# DriveModule.net
KiCad netlist of a schematic drawn in Altium Designer
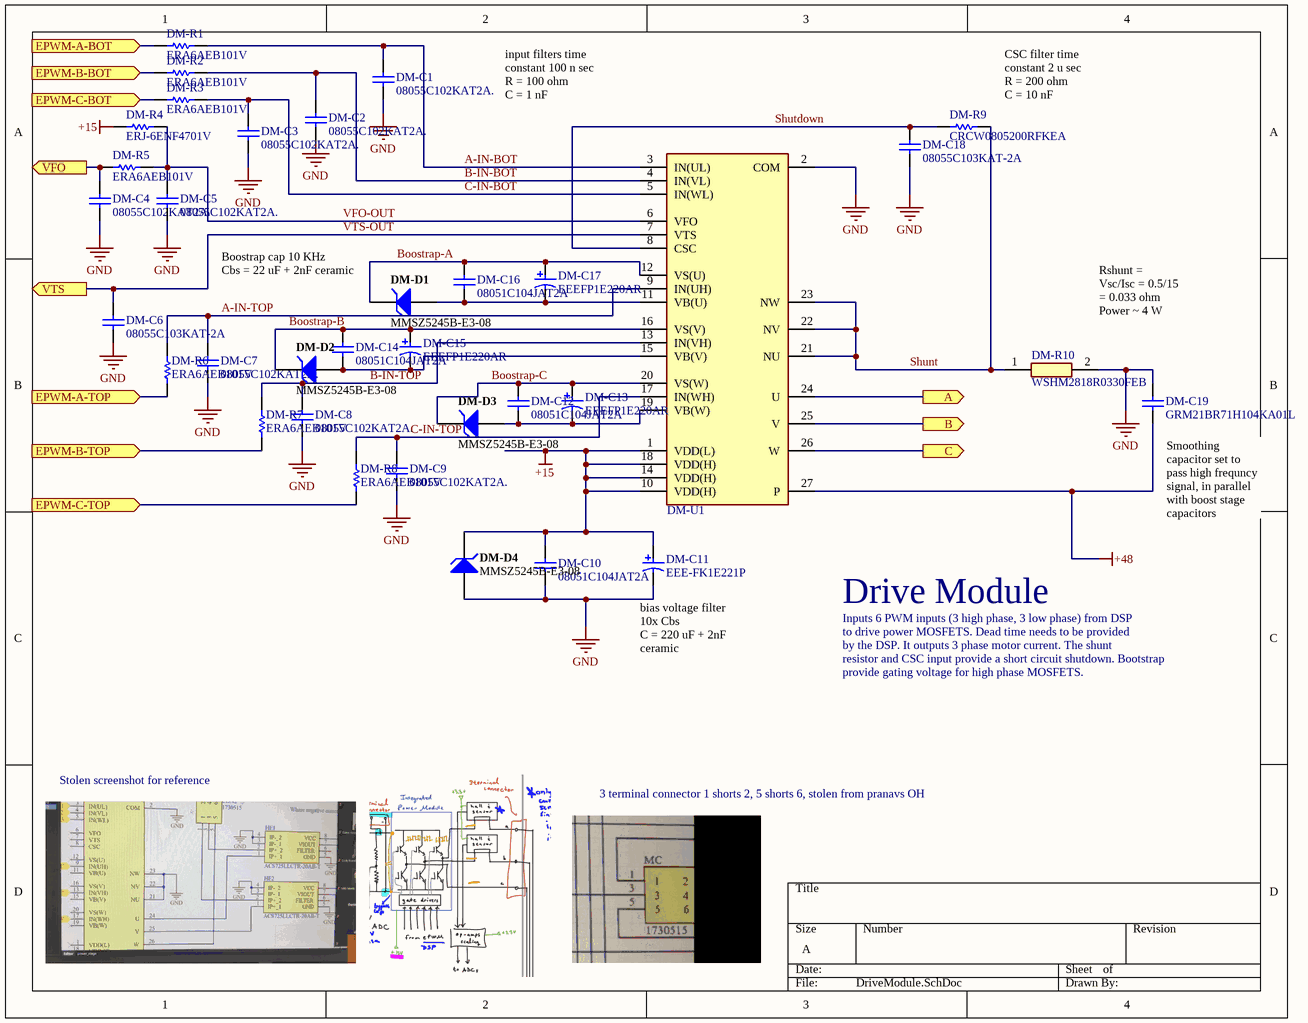
[diagram p0: DriveModule.SchDoc]

(export (version "E")
  (design (tool "Eeschema 10.0.6"))
  (components
    (comp (ref "DM-C1")
      (value "08055C102KAT2A.")
      (footprint "CAPC2013X94X50ML20T25")
      (description "1 nF cap")
      (fields (field (name "MANUFACTURER") "AVX Interconnect / Elco"))
      (libsource (lib "Altium Content Vault") (part "CAP"))
    )
    (comp (ref "DM-C2")
      (value "08055C102KAT2A.")
      (footprint "CAPC2013X94X50ML20T25")
      (description "1 nF cap")
      (fields (field (name "MANUFACTURER") "AVX Interconnect / Elco"))
      (libsource (lib "Altium Content Vault") (part "CAP"))
    )
    (comp (ref "DM-C3")
      (value "08055C102KAT2A.")
      (footprint "CAPC2013X94X50ML20T25")
      (description "1 nF cap")
      (fields (field (name "MANUFACTURER") "AVX Interconnect / Elco"))
      (libsource (lib "Altium Content Vault") (part "CAP"))
    )
    (comp (ref "DM-C4")
      (value "08055C102KAT2A.")
      (footprint "CAPC2013X94X50ML20T25")
      (description "1 nF cap")
      (fields (field (name "MANUFACTURER") "AVX Interconnect / Elco"))
      (libsource (lib "Altium Content Vault") (part "CAP"))
    )
    (comp (ref "DM-C5")
      (value "08055C102KAT2A.")
      (footprint "CAPC2013X94X50ML20T25")
      (description "1 nF cap")
      (fields (field (name "MANUFACTURER") "AVX Interconnect / Elco"))
      (libsource (lib "Altium Content Vault") (part "CAP"))
    )
    (comp (ref "DM-C6")
      (value "08055C103KAT-2A")
      (footprint "CAPC2013X94X50NL20T25")
      (description "10 nF cap")
      (fields (field (name "MANUFACTURER") "AVX Interconnect / Elco"))
      (libsource (lib "Altium Content Vault") (part "CAP"))
    )
    (comp (ref "DM-C7")
      (value "08055C102KAT2A.")
      (footprint "CAPC2013X94X50ML20T25")
      (description "1 nF cap")
      (fields (field (name "MANUFACTURER") "AVX Interconnect / Elco"))
      (libsource (lib "Altium Content Vault") (part "CAP"))
    )
    (comp (ref "DM-C8")
      (value "08055C102KAT2A.")
      (footprint "CAPC2013X94X50ML20T25")
      (description "1 nF cap")
      (fields (field (name "MANUFACTURER") "AVX Interconnect / Elco"))
      (libsource (lib "Altium Content Vault") (part "CAP"))
    )
    (comp (ref "DM-C9")
      (value "08055C102KAT2A.")
      (footprint "CAPC2013X94X50ML20T25")
      (description "1 nF cap")
      (fields (field (name "MANUFACTURER") "AVX Interconnect / Elco"))
      (libsource (lib "Altium Content Vault") (part "CAP"))
    )
    (comp (ref "DM-C10")
      (value "08051C104JAT2A")
      (footprint "CAPC2013X94X50ML20T25")
      (fields (field (name "MANUFACTURER") "AVX Interconnect / Elco"))
      (libsource (lib "Altium Content Vault") (part "CAP"))
    )
    (comp (ref "DM-C11")
      (value "EEE-FK1E221P")
      (footprint "PNSC-EEE-FK1E221P_N")
      (fields (field (name "MANUFACTURER") "Panasonic"))
      (libsource (lib "Altium Content Vault") (part "CAP-P-2"))
    )
    (comp (ref "DM-C12")
      (value "08051C104JAT2A")
      (footprint "CAPC2013X94X50ML20T25")
      (fields (field (name "MANUFACTURER") "AVX Interconnect / Elco"))
      (libsource (lib "Altium Content Vault") (part "CAP"))
    )
    (comp (ref "DM-C13")
      (value "EEEFP1E220AR")
      (footprint "PNSC-FP-V-C_V")
      (fields (field (name "MANUFACTURER") "Panasonic"))
      (libsource (lib "Altium Content Vault") (part "CAP-P-2"))
    )
    (comp (ref "DM-C14")
      (value "08051C104JAT2A")
      (footprint "CAPC2013X94X50ML20T25")
      (fields (field (name "MANUFACTURER") "AVX Interconnect / Elco"))
      (libsource (lib "Altium Content Vault") (part "CAP"))
    )
    (comp (ref "DM-C15")
      (value "EEEFP1E220AR")
      (footprint "PNSC-FP-V-C_V")
      (fields (field (name "MANUFACTURER") "Panasonic"))
      (libsource (lib "Altium Content Vault") (part "CAP-P-2"))
    )
    (comp (ref "DM-C16")
      (value "08051C104JAT2A")
      (footprint "CAPC2013X94X50ML20T25")
      (fields (field (name "MANUFACTURER") "AVX Interconnect / Elco"))
      (libsource (lib "Altium Content Vault") (part "CAP"))
    )
    (comp (ref "DM-C17")
      (value "EEEFP1E220AR")
      (footprint "PNSC-FP-V-C_V")
      (fields (field (name "MANUFACTURER") "Panasonic"))
      (libsource (lib "Altium Content Vault") (part "CAP-P-2"))
    )
    (comp (ref "DM-C18")
      (value "08055C103KAT-2A")
      (footprint "CAPC2013X94X50NL20T25")
      (description "10 nF cap")
      (fields (field (name "MANUFACTURER") "AVX Interconnect / Elco"))
      (libsource (lib "Altium Content Vault") (part "CAP"))
    )
    (comp (ref "DM-C19")
      (value "GRM21BR71H104KA01L")
      (footprint "CAPC2013X135X45ML10T25")
      (description "Chip Capacitor, 0.1 uF, +/- 10%, 50 V, -55 to 125 degC, 0805 (2012 Metric), RoHS, Tape and Reel")
      (fields (field (name "VOLTAGE") "50V") (field (name "TOLERANCE") "10%"))
      (libsource (lib "Altium Content Vault") (part "CAP-NP-2"))
    )
    (comp (ref "DM-D1")
      (value "MMSZ5245B-E3-08")
      (footprint "VISH-SOD-123-2_V")
      (description "Small Signal Zener Diode, 15 V +/- 5%, -55 to 155 degC, 2-Pin SOD-123, RoHS, Tape and Reel")
      (fields (field (name "MANUFACTURER") "Vishay Semiconductor") (field (name "TOLERANCE") "+/- 5%"))
      (libsource (lib "Altium Content Vault") (part "VISH-DZEN_A1K2-2"))
    )
    (comp (ref "DM-D2")
      (value "MMSZ5245B-E3-08")
      (footprint "VISH-SOD-123-2_V")
      (description "Small Signal Zener Diode, 15 V +/- 5%, -55 to 155 degC, 2-Pin SOD-123, RoHS, Tape and Reel")
      (fields (field (name "MANUFACTURER") "Vishay Semiconductor") (field (name "TOLERANCE") "+/- 5%"))
      (libsource (lib "Altium Content Vault") (part "VISH-DZEN_A1K2-2"))
    )
    (comp (ref "DM-D3")
      (value "MMSZ5245B-E3-08")
      (footprint "VISH-SOD-123-2_V")
      (description "Small Signal Zener Diode, 15 V +/- 5%, -55 to 155 degC, 2-Pin SOD-123, RoHS, Tape and Reel")
      (fields (field (name "MANUFACTURER") "Vishay Semiconductor") (field (name "TOLERANCE") "+/- 5%"))
      (libsource (lib "Altium Content Vault") (part "VISH-DZEN_A1K2-2"))
    )
    (comp (ref "DM-D4")
      (value "MMSZ5245B-E3-08")
      (footprint "VISH-SOD-123-2_V")
      (description "Small Signal Zener Diode, 15 V +/- 5%, -55 to 155 degC, 2-Pin SOD-123, RoHS, Tape and Reel")
      (fields (field (name "MANUFACTURER") "Vishay Semiconductor") (field (name "TOLERANCE") "+/- 5%"))
      (libsource (lib "Altium Content Vault") (part "VISH-DZEN_A1K2-2"))
    )
    (comp (ref "DM-R1")
      (value "ERA6AEB101V")
      (footprint "RESC2013X60X40ML20T25")
      (description "100 ohm resistor")
      (fields (field (name "MANUFACTURER") "Panasonic"))
      (libsource (lib "Altium Content Vault") (part "RES"))
    )
    (comp (ref "DM-R2")
      (value "ERA6AEB101V")
      (footprint "RESC2013X60X40ML20T25")
      (description "100 ohm resistor")
      (fields (field (name "MANUFACTURER") "Panasonic"))
      (libsource (lib "Altium Content Vault") (part "RES"))
    )
    (comp (ref "DM-R3")
      (value "ERA6AEB101V")
      (footprint "RESC2013X60X40ML20T25")
      (description "100 ohm resistor")
      (fields (field (name "MANUFACTURER") "Panasonic"))
      (libsource (lib "Altium Content Vault") (part "RES"))
    )
    (comp (ref "DM-R4")
      (value "ERJ-6ENF4701V")
      (footprint "RESC2013X70X40NL20T20")
      (description "Chip Resistor, 4.7 KOhm, +/- 1%, 0.125 W, -55 to 155 degC, 0805 (2012 Metric), RoHS, Tape and Reel")
      (fields (field (name "MANUFACTURER") "Panasonic"))
      (libsource (lib "Altium Content Vault") (part "RES-2"))
    )
    (comp (ref "DM-R5")
      (value "ERA6AEB101V")
      (footprint "RESC2013X60X40ML20T25")
      (fields (field (name "MANUFACTURER") "Panasonic"))
      (libsource (lib "Altium Content Vault") (part "RES"))
    )
    (comp (ref "DM-R6")
      (value "ERA6AEB101V")
      (footprint "RESC2013X60X40ML20T25")
      (description "100 ohm resistor")
      (fields (field (name "MANUFACTURER") "Panasonic"))
      (libsource (lib "Altium Content Vault") (part "RES"))
    )
    (comp (ref "DM-R7")
      (value "ERA6AEB101V")
      (footprint "RESC2013X60X40ML20T25")
      (description "100 ohm resistor")
      (fields (field (name "MANUFACTURER") "Panasonic"))
      (libsource (lib "Altium Content Vault") (part "RES"))
    )
    (comp (ref "DM-R8")
      (value "ERA6AEB101V")
      (footprint "RESC2013X60X40ML20T25")
      (description "100 ohm resistor")
      (fields (field (name "MANUFACTURER") "Panasonic"))
      (libsource (lib "Altium Content Vault") (part "RES"))
    )
    (comp (ref "DM-R9")
      (value "CRCW0805200RFKEA")
      (footprint "RESC2013X50X30NL20T20")
      (description "200 ohm resistor")
      (fields (field (name "MANUFACTURER") "Vishay Dale"))
      (libsource (lib "Altium Content Vault") (part "RES"))
    )
    (comp (ref "DM-R10")
      (value "WSHM2818R0330FEB")
      (footprint "SamacSys:WSHM2818R0330FEB")
      (description "Resistor")
      (fields (field (name "MOUSER PART NUMBER") "71-WSHM2818R0330FEB"))
      (libsource (lib "*") (part "WSHM2818R0330FEB"))
    )
    (comp (ref "DM-U1")
      (value "FNB34060T")
      (footprint "FNB34060T")
      (description "3 phase power module")
      (libsource (lib "ee_453_yourname") (part "FNB34060T"))
    )
  )
  (nets
    (net (code "1") (name "+15") (class "Default")
      (node (ref "DM-C10") (pin "2") (pinfunction "2_2") (pintype "passive"))
      (node (ref "DM-C11") (pin "1") (pinfunction "1_1") (pintype "passive"))
      (node (ref "DM-D4") (pin "2") (pinfunction "K_2") (pintype "passive"))
      (node (ref "DM-R4") (pin "1") (pinfunction "1_1") (pintype "passive"))
      (node (ref "DM-U1") (pin "1") (pinfunction "VDD(L)_1") (pintype "power_in"))
      (node (ref "DM-U1") (pin "10") (pinfunction "VDD(H)_10") (pintype "power_in"))
      (node (ref "DM-U1") (pin "14") (pinfunction "VDD(H)_14") (pintype "power_in"))
      (node (ref "DM-U1") (pin "18") (pinfunction "VDD(H)_18") (pintype "power_in"))
    )
    (net (code "2") (name "+48") (class "Default")
      (node (ref "DM-C19") (pin "1") (pinfunction "1_1") (pintype "passive"))
      (node (ref "DM-U1") (pin "27") (pinfunction "P_27") (pintype "passive"))
    )
    (net (code "3") (name "/A") (class "Default")
      (node (ref "DM-U1") (pin "24") (pinfunction "U_24") (pintype "passive"))
    )
    (net (code "4") (name "/A-IN-BOT") (class "Default")
      (node (ref "DM-C1") (pin "2") (pinfunction "2_2") (pintype "passive"))
      (node (ref "DM-R1") (pin "2") (pinfunction "2_2") (pintype "passive"))
      (node (ref "DM-U1") (pin "3") (pinfunction "IN(UL)_3") (pintype "passive"))
    )
    (net (code "5") (name "/A-IN-TOP") (class "Default")
      (node (ref "DM-C7") (pin "2") (pinfunction "2_2") (pintype "passive"))
      (node (ref "DM-R6") (pin "2") (pinfunction "2_2") (pintype "passive"))
      (node (ref "DM-U1") (pin "9") (pinfunction "IN(UH)_9") (pintype "passive"))
    )
    (net (code "6") (name "/B") (class "Default")
      (node (ref "DM-U1") (pin "25") (pinfunction "V_25") (pintype "passive"))
    )
    (net (code "7") (name "/B-IN-BOT") (class "Default")
      (node (ref "DM-C2") (pin "2") (pinfunction "2_2") (pintype "passive"))
      (node (ref "DM-R2") (pin "2") (pinfunction "2_2") (pintype "passive"))
      (node (ref "DM-U1") (pin "4") (pinfunction "IN(VL)_4") (pintype "passive"))
    )
    (net (code "8") (name "/B-IN-TOP") (class "Default")
      (node (ref "DM-C8") (pin "2") (pinfunction "2_2") (pintype "passive"))
      (node (ref "DM-R7") (pin "2") (pinfunction "2_2") (pintype "passive"))
      (node (ref "DM-U1") (pin "13") (pinfunction "IN(VH)_13") (pintype "passive"))
    )
    (net (code "9") (name "/Boostrap-A") (class "Default")
      (node (ref "DM-C16") (pin "2") (pinfunction "2_2") (pintype "passive"))
      (node (ref "DM-C17") (pin "1") (pinfunction "1_1") (pintype "passive"))
      (node (ref "DM-D1") (pin "2") (pinfunction "K_2") (pintype "passive"))
      (node (ref "DM-U1") (pin "12") (pinfunction "VS(U)_12") (pintype "power_in"))
    )
    (net (code "10") (name "/Boostrap-B") (class "Default")
      (node (ref "DM-C14") (pin "2") (pinfunction "2_2") (pintype "passive"))
      (node (ref "DM-C15") (pin "1") (pinfunction "1_1") (pintype "passive"))
      (node (ref "DM-D2") (pin "2") (pinfunction "K_2") (pintype "passive"))
      (node (ref "DM-U1") (pin "16") (pinfunction "VS(V)_16") (pintype "power_in"))
    )
    (net (code "11") (name "/Boostrap-C") (class "Default")
      (node (ref "DM-C12") (pin "2") (pinfunction "2_2") (pintype "passive"))
      (node (ref "DM-C13") (pin "1") (pinfunction "1_1") (pintype "passive"))
      (node (ref "DM-D3") (pin "2") (pinfunction "K_2") (pintype "passive"))
      (node (ref "DM-U1") (pin "20") (pinfunction "VS(W)_20") (pintype "power_in"))
    )
    (net (code "12") (name "/C") (class "Default")
      (node (ref "DM-U1") (pin "26") (pinfunction "W_26") (pintype "passive"))
    )
    (net (code "13") (name "/C-IN-BOT") (class "Default")
      (node (ref "DM-C3") (pin "2") (pinfunction "2_2") (pintype "passive"))
      (node (ref "DM-R3") (pin "2") (pinfunction "2_2") (pintype "passive"))
      (node (ref "DM-U1") (pin "5") (pinfunction "IN(WL)_5") (pintype "passive"))
    )
    (net (code "14") (name "/C-IN-TOP") (class "Default")
      (node (ref "DM-C9") (pin "2") (pinfunction "2_2") (pintype "passive"))
      (node (ref "DM-R8") (pin "2") (pinfunction "2_2") (pintype "passive"))
      (node (ref "DM-U1") (pin "17") (pinfunction "IN(WH)_17") (pintype "passive"))
    )
    (net (code "15") (name "/EPWM-A-BOT") (class "Default")
      (node (ref "DM-R1") (pin "1") (pinfunction "1_1") (pintype "passive"))
    )
    (net (code "16") (name "/EPWM-A-TOP") (class "Default")
      (node (ref "DM-R6") (pin "1") (pinfunction "1_1") (pintype "passive"))
    )
    (net (code "17") (name "/EPWM-B-BOT") (class "Default")
      (node (ref "DM-R2") (pin "1") (pinfunction "1_1") (pintype "passive"))
    )
    (net (code "18") (name "/EPWM-B-TOP") (class "Default")
      (node (ref "DM-R7") (pin "1") (pinfunction "1_1") (pintype "passive"))
    )
    (net (code "19") (name "/EPWM-C-BOT") (class "Default")
      (node (ref "DM-R3") (pin "1") (pinfunction "1_1") (pintype "passive"))
    )
    (net (code "20") (name "/EPWM-C-TOP") (class "Default")
      (node (ref "DM-R8") (pin "1") (pinfunction "1_1") (pintype "passive"))
    )
    (net (code "21") (name "/Shunt") (class "Default")
      (node (ref "DM-R10") (pin "1") (pinfunction "1_1") (pintype "passive"))
      (node (ref "DM-R9") (pin "1") (pinfunction "1_1") (pintype "passive"))
      (node (ref "DM-U1") (pin "21") (pinfunction "NU_21") (pintype "passive"))
      (node (ref "DM-U1") (pin "22") (pinfunction "NV_22") (pintype "passive"))
      (node (ref "DM-U1") (pin "23") (pinfunction "NW_23") (pintype "passive"))
    )
    (net (code "22") (name "/Shutdown") (class "Default")
      (node (ref "DM-C18") (pin "2") (pinfunction "2_2") (pintype "passive"))
      (node (ref "DM-R9") (pin "2") (pinfunction "2_2") (pintype "passive"))
      (node (ref "DM-U1") (pin "8") (pinfunction "CSC_8") (pintype "passive"))
    )
    (net (code "23") (name "/VFO") (class "Default")
      (node (ref "DM-C4") (pin "2") (pinfunction "2_2") (pintype "passive"))
      (node (ref "DM-R5") (pin "1") (pinfunction "1_1") (pintype "passive"))
    )
    (net (code "24") (name "/VFO-OUT") (class "Default")
      (node (ref "DM-C5") (pin "2") (pinfunction "2_2") (pintype "passive"))
      (node (ref "DM-R4") (pin "2") (pinfunction "2_2") (pintype "passive"))
      (node (ref "DM-R5") (pin "2") (pinfunction "2_2") (pintype "passive"))
      (node (ref "DM-U1") (pin "6") (pinfunction "VFO_6") (pintype "passive"))
    )
    (net (code "25") (name "/VTS-OUT") (class "Default")
      (node (ref "DM-C6") (pin "2") (pinfunction "2_2") (pintype "passive"))
      (node (ref "DM-U1") (pin "7") (pinfunction "VTS_7") (pintype "passive"))
    )
    (net (code "26") (name "GND") (class "Default")
      (node (ref "DM-C1") (pin "1") (pinfunction "1_1") (pintype "passive"))
      (node (ref "DM-C10") (pin "1") (pinfunction "1_1") (pintype "passive"))
      (node (ref "DM-C11") (pin "2") (pinfunction "2_2") (pintype "passive"))
      (node (ref "DM-C18") (pin "1") (pinfunction "1_1") (pintype "passive"))
      (node (ref "DM-C19") (pin "2") (pinfunction "2_2") (pintype "passive"))
      (node (ref "DM-C2") (pin "1") (pinfunction "1_1") (pintype "passive"))
      (node (ref "DM-C3") (pin "1") (pinfunction "1_1") (pintype "passive"))
      (node (ref "DM-C4") (pin "1") (pinfunction "1_1") (pintype "passive"))
      (node (ref "DM-C5") (pin "1") (pinfunction "1_1") (pintype "passive"))
      (node (ref "DM-C6") (pin "1") (pinfunction "1_1") (pintype "passive"))
      (node (ref "DM-C7") (pin "1") (pinfunction "1_1") (pintype "passive"))
      (node (ref "DM-C8") (pin "1") (pinfunction "1_1") (pintype "passive"))
      (node (ref "DM-C9") (pin "1") (pinfunction "1_1") (pintype "passive"))
      (node (ref "DM-D4") (pin "1") (pinfunction "A_1") (pintype "passive"))
      (node (ref "DM-R10") (pin "2") (pinfunction "2_2") (pintype "passive"))
      (node (ref "DM-U1") (pin "2") (pinfunction "COM_2") (pintype "power_in"))
    )
    (net (code "27") (name "Net-(DM-D1-A)") (class "Default")
      (node (ref "DM-C16") (pin "1") (pinfunction "1_1") (pintype "passive"))
      (node (ref "DM-C17") (pin "2") (pinfunction "2_2") (pintype "passive"))
      (node (ref "DM-D1") (pin "1") (pinfunction "A_1") (pintype "passive"))
      (node (ref "DM-U1") (pin "11") (pinfunction "VB(U)_11") (pintype "power_in"))
    )
    (net (code "28") (name "Net-(DM-D2-A)") (class "Default")
      (node (ref "DM-C14") (pin "1") (pinfunction "1_1") (pintype "passive"))
      (node (ref "DM-C15") (pin "2") (pinfunction "2_2") (pintype "passive"))
      (node (ref "DM-D2") (pin "1") (pinfunction "A_1") (pintype "passive"))
      (node (ref "DM-U1") (pin "15") (pinfunction "VB(V)_15") (pintype "power_in"))
    )
    (net (code "29") (name "Net-(DM-D3-A)") (class "Default")
      (node (ref "DM-C12") (pin "1") (pinfunction "1_1") (pintype "passive"))
      (node (ref "DM-C13") (pin "2") (pinfunction "2_2") (pintype "passive"))
      (node (ref "DM-D3") (pin "1") (pinfunction "A_1") (pintype "passive"))
      (node (ref "DM-U1") (pin "19") (pinfunction "VB(W)_19") (pintype "power_in"))
    )
  )
)
